# Schematic_Rev1.net
KiCad netlist of a schematic drawn in Altium Designer
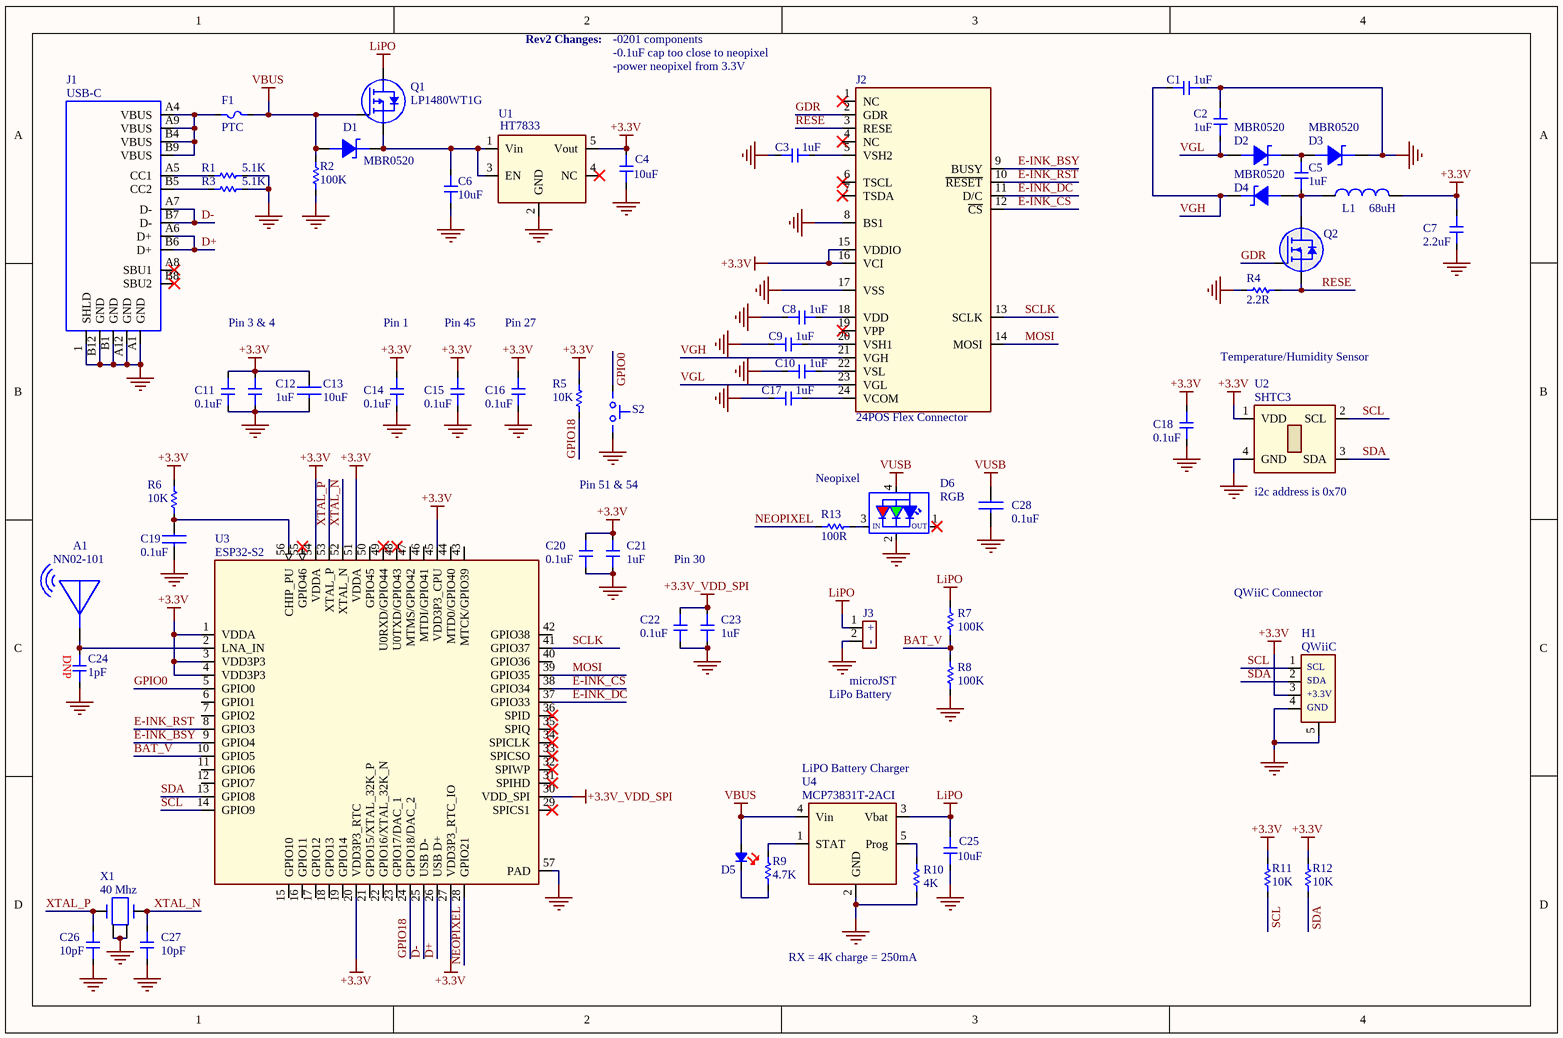
[diagram p0: Schematic_Rev1.SchDoc]

(export (version "E")
  (design (tool "Eeschema 10.0.6"))
  (components
    (comp (ref "A1")
      (value "NN02-101")
      (footprint "NN02-101")
      (description "Antenna Chip 2.4Gig")
      (fields (field (name "MANUFACTURER") "Ignion"))
      (libsource (lib "MAR") (part "NN02-101"))
    )
    (comp (ref "C1")
      (value "1uF")
      (footprint "CAPC1005X56N")
      (description "CAP 1uF 0402")
      (libsource (lib "MAR") (part "CAP_0402"))
    )
    (comp (ref "C2")
      (value "1uF")
      (footprint "CAPC1005X56N")
      (description "CAP 1uF 0402")
      (libsource (lib "MAR") (part "CAP_0402"))
    )
    (comp (ref "C3")
      (value "1uF")
      (footprint "CAPC1005X56N")
      (description "CAP 1uF 0402")
      (libsource (lib "MAR") (part "CAP_0402"))
    )
    (comp (ref "C4")
      (value "10uF")
      (footprint "CAPC2012X140N")
      (description "CAP 10uF 0805")
      (libsource (lib "MAR") (part "CAP_0805"))
    )
    (comp (ref "C5")
      (value "1uF")
      (footprint "CAPC1005X56N")
      (description "CAP 1uF 0402")
      (libsource (lib "MAR") (part "CAP_0402"))
    )
    (comp (ref "C6")
      (value "10uF")
      (footprint "CAPC2012X140N")
      (description "CAP 10uF 0805")
      (libsource (lib "MAR") (part "CAP_0805"))
    )
    (comp (ref "C7")
      (value "2.2uF")
      (footprint "CAPC1608X09L")
      (description "CAP 2.2uF 0603")
      (libsource (lib "MAR") (part "CAP_0402"))
    )
    (comp (ref "C8")
      (value "1uF")
      (footprint "CAPC1005X56N")
      (description "CAP 1uF 0402")
      (libsource (lib "MAR") (part "CAP_0402"))
    )
    (comp (ref "C9")
      (value "1uF")
      (footprint "CAPC1005X56N")
      (description "CAP 1uF 0402")
      (libsource (lib "MAR") (part "CAP_0402"))
    )
    (comp (ref "C10")
      (value "1uF")
      (footprint "CAPC1005X56N")
      (description "CAP 1uF 0402")
      (libsource (lib "MAR") (part "CAP_0402"))
    )
    (comp (ref "C11")
      (value "0.1uF")
      (footprint "CAPC1005X56N")
      (description "CAP 0.1uF 0402")
      (libsource (lib "MAR") (part "CAP_0402"))
    )
    (comp (ref "C12")
      (value "1uF")
      (footprint "CAPC1005X56N")
      (description "CAP 1uF 0402")
      (libsource (lib "MAR") (part "CAP_0402"))
    )
    (comp (ref "C13")
      (value "10uF")
      (footprint "CAPC2012X140N")
      (description "CAP 10uF 0805")
      (libsource (lib "") (part "CAP_0805_1"))
    )
    (comp (ref "C14")
      (value "0.1uF")
      (footprint "CAPC1005X56N")
      (description "CAP 0.1uF 0402")
      (libsource (lib "MAR") (part "CAP_0402"))
    )
    (comp (ref "C15")
      (value "0.1uF")
      (footprint "CAPC1005X56N")
      (description "CAP 0.1uF 0402")
      (libsource (lib "MAR") (part "CAP_0402"))
    )
    (comp (ref "C16")
      (value "0.1uF")
      (footprint "CAPC1005X56N")
      (description "CAP 0.1uF 0402")
      (libsource (lib "MAR") (part "CAP_0402"))
    )
    (comp (ref "C17")
      (value "1uF")
      (footprint "CAPC1005X56N")
      (description "CAP 1uF 0402")
      (libsource (lib "MAR") (part "CAP_0402"))
    )
    (comp (ref "C18")
      (value "0.1uF")
      (footprint "CAPC1005X56N")
      (description "CAP 0.1uF 0402")
      (libsource (lib "MAR") (part "CAP_0402"))
    )
    (comp (ref "C19")
      (value "0.1uF")
      (footprint "CAPC1005X56N")
      (description "CAP 0.1uF 0402")
      (fields (field (name "LCSC_PART_NUMBER") "C344190") (field (name "MANUFACTURER") "CCTC"))
      (libsource (lib "") (part "CAP_0402_1"))
    )
    (comp (ref "C20")
      (value "0.1uF")
      (footprint "CAPC1005X56N")
      (description "CAP 0.1uF 0402")
      (libsource (lib "MAR") (part "CAP_0402"))
    )
    (comp (ref "C21")
      (value "1uF")
      (footprint "CAPC1005X56N")
      (description "CAP 1uF 0402")
      (libsource (lib "MAR") (part "CAP_0402"))
    )
    (comp (ref "C22")
      (value "0.1uF")
      (footprint "CAPC1005X56N")
      (description "CAP 0.1uF 0402")
      (libsource (lib "MAR") (part "CAP_0402"))
    )
    (comp (ref "C23")
      (value "1uF")
      (footprint "CAPC1005X56N")
      (description "CAP 0.1uF 0402")
      (libsource (lib "MAR") (part "CAP_0402"))
    )
    (comp (ref "C24")
      (value "1pF")
      (footprint "CAPC1005X56N")
      (description "CAP 1pF 0402")
      (libsource (lib "MAR") (part "CAP_0402"))
    )
    (comp (ref "C25")
      (value "10uF")
      (footprint "CAPC2012X140N")
      (description "CAP 10uF 0805")
      (libsource (lib "MAR") (part "CAP_0805"))
    )
    (comp (ref "C26")
      (value "10pF")
      (footprint "CAPC1005X56N")
      (description "CAP 10pF 0402")
      (libsource (lib "MAR") (part "CAP_0402"))
    )
    (comp (ref "C27")
      (value "10pF")
      (footprint "CAPC1005X56N")
      (description "CAP 10pF 0402")
      (libsource (lib "MAR") (part "CAP_0402"))
    )
    (comp (ref "C28")
      (value "0.1uF")
      (footprint "CAPC1005X56N")
      (description "CAP 0.1uF 0402")
      (libsource (lib "") (part "CAP_0402_1"))
    )
    (comp (ref "D1")
      (value "MBR0520")
      (footprint "SOD123")
      (description "DIODE SCHOTTKY 20V 500MA SOD-123")
      (fields (field (name "MANUFACTURER") "Micro") (field (name "PART_NUMBER") "C78746"))
      (libsource (lib "MAR") (part "MBR0520-TP"))
    )
    (comp (ref "D2")
      (value "MBR0520")
      (footprint "SOD123")
      (description "DIODE SCHOTTKY 20V 500MA SOD-123")
      (fields (field (name "MANUFACTURER") "Micro") (field (name "PART_NUMBER") "C78746"))
      (libsource (lib "MAR") (part "MBR0520-TP"))
    )
    (comp (ref "D3")
      (value "MBR0520")
      (footprint "SOD123")
      (description "DIODE SCHOTTKY 20V 500MA SOD-123")
      (fields (field (name "MANUFACTURER") "Micro") (field (name "PART_NUMBER") "C78746"))
      (libsource (lib "MAR") (part "MBR0520-TP"))
    )
    (comp (ref "D4")
      (value "MBR0520")
      (footprint "SOD123")
      (description "DIODE SCHOTTKY 20V 500MA SOD-123")
      (fields (field (name "MANUFACTURER") "Micro") (field (name "PART_NUMBER") "C78746"))
      (libsource (lib "MAR") (part "MBR0520-TP"))
    )
    (comp (ref "D5")
      (value "Red Led")
      (footprint "LED1005X40N-Red")
      (description "LED Red 0402")
      (fields (field (name "PART_NUMBER") "C364556") (field (name "MANUFACTURER") "Lite-On"))
      (libsource (lib "MAR") (part "LED_0402_SMALL_Red"))
    )
    (comp (ref "D6")
      (value "RGB")
      (footprint "WS2812B-2020")
      (description "LED,RGB,NEOPIXEL,WS2818B 2020")
      (fields (field (name "PART_NUMBER") "4684") (field (name "MANUFACTURER") "Adafruit"))
      (libsource (lib "MAR") (part "WS2812B-2020"))
    )
    (comp (ref "F1")
      (value "TLC-PSMD050")
      (footprint "PTC2012X70L")
      (description "PTC FUSE 500mA hold, 1A trip")
      (fields (field (name "MANUFACTURER") "TLC") (field (name "PART_NUMBER") "C261942"))
      (libsource (lib "MAR") (part "PTC_FUSE"))
    )
    (comp (ref "H1")
      (value "QWiiC")
      (footprint "SM04B-SRSS-TB")
      (description "CONN HEADER 4POS .100 R/A QWIIC")
      (fields (field (name "MANUFACTURER") "JST") (field (name "PART_NUMBER") "PRT-14417"))
      (libsource (lib "MAR") (part "SM04B-SRSS-TB"))
    )
    (comp (ref "J1")
      (value "USB-C")
      (footprint "TYPE-C-31-M-12")
      (description "CONN RECPT USB-C")
      (fields (field (name "MANUFACTURER") "KHE") (field (name "PART_NUMBER") "C165948"))
      (libsource (lib "MAR") (part "USB-C"))
    )
    (comp (ref "J2")
      (value "24POS Flex Connector")
      (footprint "687124182122")
      (description "CONN FFC TOP/BOT 24POS 0.50MM R/A")
      (fields (field (name "MANUFACTURER") "Wurth") (field (name "PART_NUMBER") "687124182122"))
      (libsource (lib "MAR") (part "687124182122"))
    )
    (comp (ref "J3")
      (value "CON2")
      (footprint "JST_Micro_2PIN")
      (description "JST MIcro CONN 2POS")
      (libsource (lib "MAR") (part "JST_Micro_CONN_2PIN"))
    )
    (comp (ref "L1")
      (value "68uH")
      (footprint "INDUCTOR, 3mmX3mm")
      (description "INDUCTOR 68uH 20% 4mmx4mm")
      (fields (field (name "PART_NUMBER") "C135265") (field (name "MANUFACTURER") "SXN"))
      (libsource (lib "MAR") (part "68uH"))
    )
    (comp (ref "Q1")
      (value "LP1480WT1G")
      (footprint "SC-70")
      (description "MOSFET P-CH 20V 1.4A SC-70")
      (fields (field (name "MANUFACTURER") "LRC") (field (name "PART_NUMBER") "C172434"))
      (libsource (lib "MAR") (part "LP1480WT1G"))
    )
    (comp (ref "Q2")
      (value "~")
      (footprint "SOT95P240X110-3N")
      (description "MOSFET N-CH 60V 300MA SOT-23")
      (fields (field (name "MANUFACTURER") "Vishay Siliconix") (field (name "PART_NUMBER") "2N7002K-T1-E3"))
      (libsource (lib "MAR") (part "2N7002K-T1-E3"))
    )
    (comp (ref "R1")
      (value "5.1K")
      (footprint "RESC1005X40L (0402 FOOTPRINT)")
      (description "RES 5.1K 0402")
      (libsource (lib "MAR") (part "RES_0402"))
    )
    (comp (ref "R2")
      (value "100K")
      (footprint "RESC1005X40L (0402 FOOTPRINT)")
      (description "RES 100K 0402")
      (libsource (lib "MAR") (part "RES_0402"))
    )
    (comp (ref "R3")
      (value "5.1K")
      (footprint "RESC1005X40L (0402 FOOTPRINT)")
      (description "RES 5.1K 0402")
      (libsource (lib "MAR") (part "RES_0402"))
    )
    (comp (ref "R4")
      (value "2.2R")
      (footprint "RESC1005X40L (0402 FOOTPRINT)")
      (description "RES 2.2R 0402")
      (libsource (lib "MAR") (part "RES_0402"))
    )
    (comp (ref "R5")
      (value "10K")
      (footprint "RESC1005X40L (0402 FOOTPRINT)")
      (description "RES 10K 0402")
      (fields (field (name "LCSC_PART_NUMBER") "C258091") (field (name "MANUFACTURER") "Guangdong"))
      (libsource (lib "MAR") (part "RES_0402"))
    )
    (comp (ref "R6")
      (value "10K")
      (footprint "RESC1005X40L (0402 FOOTPRINT)")
      (description "RES 10K 0402")
      (fields (field (name "LCSC_PART_NUMBER") "C258091") (field (name "MANUFACTURER") "Guangdong"))
      (libsource (lib "MAR") (part "RES_0402"))
    )
    (comp (ref "R7")
      (value "100K")
      (footprint "RESC1005X40L (0402 FOOTPRINT)")
      (description "RES 100K 0402")
      (libsource (lib "MAR") (part "RES_0402"))
    )
    (comp (ref "R8")
      (value "100K")
      (footprint "RESC1005X40L (0402 FOOTPRINT)")
      (description "RES 100K 0402")
      (libsource (lib "MAR") (part "RES_0402"))
    )
    (comp (ref "R9")
      (value "4.7K")
      (footprint "RESC1005X40L (0402 FOOTPRINT)")
      (description "RES 4.7K 0402")
      (libsource (lib "MAR") (part "RES_0402"))
    )
    (comp (ref "R10")
      (value "4K")
      (footprint "RESC1005X40L (0402 FOOTPRINT)")
      (description "RES 4K 0402")
      (libsource (lib "MAR") (part "RES_0402"))
    )
    (comp (ref "R11")
      (value "10K")
      (footprint "RESC1005X40L (0402 FOOTPRINT)")
      (description "RES 10K 0402")
      (libsource (lib "MAR") (part "RES_0402"))
    )
    (comp (ref "R12")
      (value "10K")
      (footprint "RESC1005X40L (0402 FOOTPRINT)")
      (description "RES 10K 0402")
      (libsource (lib "MAR") (part "RES_0402"))
    )
    (comp (ref "R13")
      (value "100R")
      (footprint "RESC1005X40L (0402 FOOTPRINT)")
      (description "RES 100R 0402")
      (fields (field (name "MANUFACTURER") "Yageo") (field (name "PARTNUMBER") "C106232"))
      (libsource (lib "MAR") (part "RES_0603"))
    )
    (comp (ref "S2")
      (value "~")
      (footprint "TS-1088R-02526")
      (description "Tactile Micro Switch")
      (fields (field (name "PART_NUMBER") "C455281") (field (name "MANUFACTURER") "XUNPU"))
      (libsource (lib "MAR") (part "TS-1088R-02526"))
    )
    (comp (ref "U1")
      (value "HT7833")
      (footprint "SOT95P280X144-5N")
      (description "IC LDO 3.3V 0.5A SOT23-5")
      (fields (field (name "MANUFACTURER") "Holtek") (field (name "PART_NUMBER") "C164106"))
      (libsource (lib "MAR") (part "HT7833"))
    )
    (comp (ref "U2")
      (value "SHTC3")
      (footprint "DFN-4 (2.0mm X 2.0mm)")
      (description "Humidity/Temperature Sensor")
      (fields (field (name "MANUFACTURER") "Sensirion") (field (name "PART_NUMBER") "SHTC3"))
      (libsource (lib "MAR") (part "SHTC3"))
    )
    (comp (ref "U3")
      (value "ESP32-S2")
      (footprint "QFN56_0.4mm pitch")
      (description "WIFI/Bluetooth, QFN-56 7x7")
      (fields (field (name "MANUFACTURER") "Espressif") (field (name "PART_NUMBER") "C529594"))
      (libsource (lib "MAR") (part "ESP32-S2"))
    )
    (comp (ref "U4")
      (value "MCP73831T-2ACI")
      (footprint "SOT95P280X144-5N")
      (description "Charger IC Lithium-Ion/Polymer SOT23-5")
      (fields (field (name "MANUFACTURER") "Microchip") (field (name "PART_NUMBER") "MCP73831T-2ACI/OT"))
      (libsource (lib "MAR") (part "MCP73831T-2ACI/OT"))
    )
    (comp (ref "X1")
      (value "40 Mhz")
      (footprint "OSC20X16")
      (description "CRYSTAL 40MHZ 10PF SMD")
      (fields (field (name "PART_NUMBER") "ECS-400-10-37B2-CKM") (field (name "MANUFACTURER") "ECS"))
      (libsource (lib "MAR") (part "40Mhz"))
    )
  )
  (nets
    (net (code "1") (name "+3.3V") (class "Default")
      (node (ref "C11") (pin "1") (pintype "passive"))
      (node (ref "C12") (pin "1") (pintype "passive"))
      (node (ref "C13") (pin "1") (pinfunction "1_1") (pintype "passive"))
      (node (ref "C14") (pin "1") (pintype "passive"))
      (node (ref "C15") (pin "1") (pintype "passive"))
      (node (ref "C16") (pin "1") (pintype "passive"))
      (node (ref "C18") (pin "1") (pintype "passive"))
      (node (ref "C20") (pin "1") (pintype "passive"))
      (node (ref "C21") (pin "1") (pintype "passive"))
      (node (ref "C4") (pin "1") (pintype "passive"))
      (node (ref "C7") (pin "1") (pintype "passive"))
      (node (ref "H1") (pin "3") (pintype "passive"))
      (node (ref "J2") (pin "15") (pinfunction "VDDIO_15") (pintype "power_in"))
      (node (ref "J2") (pin "16") (pinfunction "VCI_16") (pintype "power_in"))
      (node (ref "L1") (pin "2") (pinfunction "2_2") (pintype "passive"))
      (node (ref "R11") (pin "2") (pintype "passive"))
      (node (ref "R12") (pin "2") (pintype "passive"))
      (node (ref "R5") (pin "1") (pintype "passive"))
      (node (ref "R6") (pin "1") (pintype "passive"))
      (node (ref "U1") (pin "5") (pinfunction "Vout_5") (pintype "passive"))
      (node (ref "U2") (pin "1") (pinfunction "VDD_1") (pintype "power_in"))
      (node (ref "U3") (pin "1") (pinfunction "VDDA_1") (pintype "power_in"))
      (node (ref "U3") (pin "20") (pinfunction "VDD3P3_RTC_20") (pintype "power_in"))
      (node (ref "U3") (pin "27") (pinfunction "VDD3P3_RTC_IO_27") (pintype "power_in"))
      (node (ref "U3") (pin "3") (pinfunction "VDD3P3_3") (pintype "power_in"))
      (node (ref "U3") (pin "4") (pinfunction "VDD3P3_4") (pintype "power_in"))
      (node (ref "U3") (pin "45") (pinfunction "VDD3P3_CPU_45") (pintype "power_in"))
      (node (ref "U3") (pin "51") (pinfunction "VDDA_51") (pintype "power_in"))
      (node (ref "U3") (pin "54") (pinfunction "VDDA_54") (pintype "power_in"))
    )
    (net (code "2") (name "+3.3V_VDD_SPI") (class "Default")
      (node (ref "C22") (pin "1") (pintype "passive"))
      (node (ref "C23") (pin "1") (pintype "passive"))
      (node (ref "U3") (pin "30") (pinfunction "VDD_SPI_30") (pintype "power_in"))
    )
    (net (code "3") (name "/BAT_V") (class "Default")
      (node (ref "R7") (pin "1") (pintype "passive"))
      (node (ref "R8") (pin "2") (pintype "passive"))
      (node (ref "U3") (pin "10") (pinfunction "GPIO5_10") (pintype "passive"))
    )
    (net (code "4") (name "/D+") (class "Default")
      (node (ref "J1") (pin "A6") (pinfunction "D+_A6") (pintype "power_in"))
      (node (ref "J1") (pin "B6") (pinfunction "D+_B6") (pintype "power_in"))
      (node (ref "U3") (pin "26") (pinfunction "USB_D+_26") (pintype "passive"))
    )
    (net (code "5") (name "/D-") (class "Default")
      (node (ref "J1") (pin "A7") (pinfunction "D-_A7") (pintype "power_in"))
      (node (ref "J1") (pin "B7") (pinfunction "D-_B7") (pintype "power_in"))
      (node (ref "U3") (pin "25") (pinfunction "USB_D-_25") (pintype "passive"))
    )
    (net (code "6") (name "/E-INK_BSY") (class "Default")
      (node (ref "J2") (pin "9") (pinfunction "BUSY_9") (pintype "passive"))
      (node (ref "U3") (pin "9") (pinfunction "GPIO4_9") (pintype "passive"))
    )
    (net (code "7") (name "/E-INK_CS") (class "Default")
      (node (ref "J2") (pin "12") (pinfunction "~{CS}_12") (pintype "passive"))
      (node (ref "U3") (pin "38") (pinfunction "GPIO34_38") (pintype "passive"))
    )
    (net (code "8") (name "/E-INK_DC") (class "Default")
      (node (ref "J2") (pin "11") (pinfunction "D/C_11") (pintype "passive"))
      (node (ref "U3") (pin "37") (pinfunction "GPIO33_37") (pintype "passive"))
    )
    (net (code "9") (name "/E-INK_RST") (class "Default")
      (node (ref "J2") (pin "10") (pinfunction "~{RESET}_10") (pintype "passive"))
      (node (ref "U3") (pin "8") (pinfunction "GPIO3_8") (pintype "passive"))
    )
    (net (code "10") (name "/GDR") (class "Default")
      (node (ref "J2") (pin "2") (pinfunction "GDR_2") (pintype "passive"))
      (node (ref "Q2") (pin "1") (pinfunction "G_1") (pintype "passive"))
    )
    (net (code "11") (name "/GPIO0") (class "Default")
      (node (ref "S2") (pin "1") (pinfunction "A_1") (pintype "passive"))
      (node (ref "U3") (pin "5") (pinfunction "GPIO0_5") (pintype "passive"))
    )
    (net (code "12") (name "/GPIO18") (class "Default")
      (node (ref "R5") (pin "2") (pintype "passive"))
      (node (ref "U3") (pin "24") (pinfunction "GPIO18/DAC_2_24") (pintype "passive"))
    )
    (net (code "13") (name "/MOSI") (class "Default")
      (node (ref "J2") (pin "14") (pinfunction "MOSI_14") (pintype "passive"))
      (node (ref "U3") (pin "39") (pinfunction "GPIO35_39") (pintype "passive"))
    )
    (net (code "14") (name "/NEOPIXEL") (class "Default")
      (node (ref "R13") (pin "2") (pintype "passive"))
      (node (ref "U3") (pin "28") (pinfunction "GPIO21_28") (pintype "passive"))
    )
    (net (code "15") (name "/RESE") (class "Default")
      (node (ref "J2") (pin "3") (pinfunction "RESE_3") (pintype "passive"))
      (node (ref "Q2") (pin "2") (pinfunction "S_2") (pintype "passive"))
      (node (ref "R4") (pin "1") (pintype "passive"))
    )
    (net (code "16") (name "/SCL") (class "Default")
      (node (ref "H1") (pin "1") (pintype "passive"))
      (node (ref "R11") (pin "1") (pintype "passive"))
      (node (ref "U2") (pin "2") (pinfunction "SCL_2") (pintype "passive"))
      (node (ref "U3") (pin "14") (pinfunction "GPIO9_14") (pintype "passive"))
    )
    (net (code "17") (name "/SCLK") (class "Default")
      (node (ref "J2") (pin "13") (pinfunction "SCLK_13") (pintype "passive"))
      (node (ref "U3") (pin "41") (pinfunction "GPIO37_41") (pintype "passive"))
    )
    (net (code "18") (name "/SDA") (class "Default")
      (node (ref "H1") (pin "2") (pintype "passive"))
      (node (ref "R12") (pin "1") (pintype "passive"))
      (node (ref "U2") (pin "3") (pinfunction "SDA_3") (pintype "passive"))
      (node (ref "U3") (pin "13") (pinfunction "GPIO8_13") (pintype "passive"))
    )
    (net (code "19") (name "/VGH") (class "Default")
      (node (ref "C1") (pin "1") (pintype "passive"))
      (node (ref "D4") (pin "1") (pinfunction "Cathode_1") (pintype "passive"))
      (node (ref "J2") (pin "21") (pinfunction "VGH_21") (pintype "passive"))
    )
    (net (code "20") (name "/VGL") (class "Default")
      (node (ref "C2") (pin "2") (pintype "passive"))
      (node (ref "D2") (pin "2") (pinfunction "Annode_2") (pintype "passive"))
      (node (ref "J2") (pin "23") (pinfunction "VGL_23") (pintype "passive"))
    )
    (net (code "21") (name "/XTAL_N") (class "Default")
      (node (ref "C27") (pin "1") (pintype "passive"))
      (node (ref "U3") (pin "52") (pinfunction "XTAL_N_52") (pintype "passive"))
      (node (ref "X1") (pin "3") (pinfunction "3_3") (pintype "passive"))
    )
    (net (code "22") (name "/XTAL_P") (class "Default")
      (node (ref "C26") (pin "1") (pintype "passive"))
      (node (ref "U3") (pin "53") (pinfunction "XTAL_P_53") (pintype "passive"))
      (node (ref "X1") (pin "1") (pinfunction "1_1") (pintype "passive"))
    )
    (net (code "23") (name "GND") (class "Default")
      (node (ref "C1") (pin "2") (pintype "passive"))
      (node (ref "C10") (pin "1") (pintype "passive"))
      (node (ref "C11") (pin "2") (pintype "passive"))
      (node (ref "C12") (pin "2") (pintype "passive"))
      (node (ref "C13") (pin "2") (pinfunction "2_2") (pintype "passive"))
      (node (ref "C14") (pin "2") (pintype "passive"))
      (node (ref "C15") (pin "2") (pintype "passive"))
      (node (ref "C16") (pin "2") (pintype "passive"))
      (node (ref "C17") (pin "1") (pintype "passive"))
      (node (ref "C18") (pin "2") (pintype "passive"))
      (node (ref "C19") (pin "2") (pinfunction "2_2") (pintype "passive"))
      (node (ref "C2") (pin "1") (pintype "passive"))
      (node (ref "C20") (pin "2") (pintype "passive"))
      (node (ref "C21") (pin "2") (pintype "passive"))
      (node (ref "C22") (pin "2") (pintype "passive"))
      (node (ref "C23") (pin "2") (pintype "passive"))
      (node (ref "C24") (pin "2") (pintype "passive"))
      (node (ref "C25") (pin "2") (pintype "passive"))
      (node (ref "C26") (pin "2") (pintype "passive"))
      (node (ref "C27") (pin "2") (pintype "passive"))
      (node (ref "C28") (pin "2") (pinfunction "2_2") (pintype "passive"))
      (node (ref "C3") (pin "1") (pintype "passive"))
      (node (ref "C4") (pin "2") (pintype "passive"))
      (node (ref "C6") (pin "2") (pintype "passive"))
      (node (ref "C7") (pin "2") (pintype "passive"))
      (node (ref "C8") (pin "1") (pintype "passive"))
      (node (ref "C9") (pin "1") (pintype "passive"))
      (node (ref "D3") (pin "1") (pinfunction "Cathode_1") (pintype "passive"))
      (node (ref "D6") (pin "2") (pinfunction "GND_2") (pintype "passive"))
      (node (ref "H1") (pin "4") (pintype "passive"))
      (node (ref "H1") (pin "5") (pintype "passive"))
      (node (ref "J1") (pin "1") (pinfunction "SHLD_1") (pintype "power_in"))
      (node (ref "J1") (pin "A1") (pinfunction "GND_A1") (pintype "power_in"))
      (node (ref "J1") (pin "A12") (pinfunction "GND_A12") (pintype "power_in"))
      (node (ref "J1") (pin "B1") (pinfunction "GND_B1") (pintype "power_in"))
      (node (ref "J1") (pin "B12") (pinfunction "GND_B12") (pintype "passive"))
      (node (ref "J2") (pin "17") (pinfunction "VSS_17") (pintype "power_in"))
      (node (ref "J2") (pin "8") (pinfunction "BS1_8") (pintype "passive"))
      (node (ref "J3") (pin "2") (pintype "passive"))
      (node (ref "R1") (pin "1") (pintype "passive"))
      (node (ref "R10") (pin "1") (pintype "passive"))
      (node (ref "R2") (pin "2") (pintype "passive"))
      (node (ref "R3") (pin "1") (pintype "passive"))
      (node (ref "R4") (pin "2") (pintype "passive"))
      (node (ref "R8") (pin "1") (pintype "passive"))
      (node (ref "S2") (pin "2") (pinfunction "B_2") (pintype "passive"))
      (node (ref "U1") (pin "2") (pinfunction "GND_2") (pintype "power_in"))
      (node (ref "U2") (pin "4") (pinfunction "GND_4") (pintype "power_in"))
      (node (ref "U3") (pin "57") (pinfunction "PAD_57") (pintype "power_in"))
      (node (ref "U4") (pin "2") (pinfunction "GND_2") (pintype "power_in"))
      (node (ref "X1") (pin "2") (pinfunction "2_2") (pintype "power_in"))
      (node (ref "X1") (pin "4") (pinfunction "4_4") (pintype "power_in"))
    )
    (net (code "24") (name "LiPO") (class "Default")
      (node (ref "C25") (pin "1") (pintype "passive"))
      (node (ref "J3") (pin "1") (pintype "passive"))
      (node (ref "Q1") (pin "3") (pinfunction "D_3") (pintype "passive"))
      (node (ref "R7") (pin "2") (pintype "passive"))
      (node (ref "U4") (pin "3") (pinfunction "Vbat_3") (pintype "passive"))
    )
    (net (code "25") (name "Net-(D1-Cathode)") (class "Default")
      (node (ref "C6") (pin "1") (pintype "passive"))
      (node (ref "D1") (pin "1") (pinfunction "Cathode_1") (pintype "passive"))
      (node (ref "Q1") (pin "2") (pinfunction "S_2") (pintype "passive"))
      (node (ref "U1") (pin "1") (pinfunction "Vin_1") (pintype "passive"))
      (node (ref "U1") (pin "3") (pinfunction "EN_3") (pintype "passive"))
    )
    (net (code "26") (name "Net-(D2-Cathode)") (class "Default")
      (node (ref "C5") (pin "1") (pintype "passive"))
      (node (ref "D2") (pin "1") (pinfunction "Cathode_1") (pintype "passive"))
      (node (ref "D3") (pin "2") (pinfunction "Annode_2") (pintype "passive"))
    )
    (net (code "27") (name "Net-(D4-Annode)") (class "Default")
      (node (ref "C5") (pin "2") (pintype "passive"))
      (node (ref "D4") (pin "2") (pinfunction "Annode_2") (pintype "passive"))
      (node (ref "L1") (pin "1") (pinfunction "1_1") (pintype "passive"))
      (node (ref "Q2") (pin "3") (pinfunction "D_3") (pintype "passive"))
    )
    (net (code "28") (name "Net-(D5-Pad1)") (class "Default")
      (node (ref "D5") (pin "1") (pintype "passive"))
      (node (ref "R9") (pin "1") (pintype "passive"))
    )
    (net (code "29") (name "Net-(D6-DIN)") (class "Default")
      (node (ref "D6") (pin "3") (pinfunction "DIN_3") (pintype "passive"))
      (node (ref "R13") (pin "1") (pintype "passive"))
    )
    (net (code "30") (name "Net-(F1-Pad2)") (class "Default")
      (node (ref "F1") (pin "2") (pintype "passive"))
      (node (ref "J1") (pin "A4") (pinfunction "VBUS_A4") (pintype "passive"))
      (node (ref "J1") (pin "A9") (pinfunction "VBUS_A9") (pintype "power_in"))
      (node (ref "J1") (pin "B4") (pinfunction "VBUS_B4") (pintype "power_in"))
      (node (ref "J1") (pin "B9") (pinfunction "VBUS_B9") (pintype "passive"))
    )
    (net (code "31") (name "Net-(J1-CC1)") (class "Default")
      (node (ref "J1") (pin "A5") (pinfunction "CC1_A5") (pintype "power_in"))
      (node (ref "R1") (pin "2") (pintype "passive"))
    )
    (net (code "32") (name "Net-(J1-CC2)") (class "Default")
      (node (ref "J1") (pin "B5") (pinfunction "CC2_B5") (pintype "power_in"))
      (node (ref "R3") (pin "2") (pintype "passive"))
    )
    (net (code "33") (name "Net-(J2-VCOM)") (class "Default")
      (node (ref "C17") (pin "2") (pintype "passive"))
      (node (ref "J2") (pin "24") (pinfunction "VCOM_24") (pintype "passive"))
    )
    (net (code "34") (name "Net-(J2-VDD)") (class "Default")
      (node (ref "C8") (pin "2") (pintype "passive"))
      (node (ref "J2") (pin "18") (pinfunction "VDD_18") (pintype "power_in"))
    )
    (net (code "35") (name "Net-(J2-VSH1)") (class "Default")
      (node (ref "C9") (pin "2") (pintype "passive"))
      (node (ref "J2") (pin "20") (pinfunction "VSH1_20") (pintype "passive"))
    )
    (net (code "36") (name "Net-(J2-VSH2)") (class "Default")
      (node (ref "C3") (pin "2") (pintype "passive"))
      (node (ref "J2") (pin "5") (pinfunction "VSH2_5") (pintype "passive"))
    )
    (net (code "37") (name "Net-(J2-VSL)") (class "Default")
      (node (ref "C10") (pin "2") (pintype "passive"))
      (node (ref "J2") (pin "22") (pinfunction "VSL_22") (pintype "passive"))
    )
    (net (code "38") (name "Net-(U3-CHIP_PU)") (class "Default")
      (node (ref "C19") (pin "1") (pinfunction "1_1") (pintype "passive"))
      (node (ref "R6") (pin "2") (pintype "passive"))
      (node (ref "U3") (pin "56") (pinfunction "CHIP_PU_56") (pintype "input"))
    )
    (net (code "39") (name "Net-(U3-LNA_IN)") (class "Default")
      (node (ref "A1") (pin "1") (pintype "passive"))
      (node (ref "C24") (pin "1") (pintype "passive"))
      (node (ref "U3") (pin "2") (pinfunction "LNA_IN_2") (pintype "passive"))
    )
    (net (code "40") (name "Net-(U4-Prog)") (class "Default")
      (node (ref "R10") (pin "2") (pintype "passive"))
      (node (ref "U4") (pin "5") (pinfunction "Prog_5") (pintype "passive"))
    )
    (net (code "41") (name "Net-(U4-STAT)") (class "Default")
      (node (ref "R9") (pin "2") (pintype "passive"))
      (node (ref "U4") (pin "1") (pinfunction "STAT_1") (pintype "passive"))
    )
    (net (code "42") (name "VBUS") (class "Default")
      (node (ref "D1") (pin "2") (pinfunction "Annode_2") (pintype "passive"))
      (node (ref "D5") (pin "2") (pintype "passive"))
      (node (ref "F1") (pin "1") (pintype "passive"))
      (node (ref "Q1") (pin "1") (pinfunction "G_1") (pintype "passive"))
      (node (ref "R2") (pin "1") (pintype "passive"))
      (node (ref "U4") (pin "4") (pinfunction "Vin_4") (pintype "passive"))
    )
    (net (code "43") (name "VUSB") (class "Default")
      (node (ref "C28") (pin "1") (pinfunction "1_1") (pintype "passive"))
      (node (ref "D6") (pin "4") (pinfunction "VDD_4") (pintype "passive"))
    )
    (net (code "44") (name "unconnected-(D6-DOUT-Pad1)") (class "Default")
      (node (ref "D6") (pin "1") (pinfunction "DOUT_1") (pintype "passive+no_connect"))
    )
    (net (code "45") (name "unconnected-(J1-SBU1-PadA8)") (class "Default")
      (node (ref "J1") (pin "A8") (pinfunction "SBU1_A8") (pintype "power_in+no_connect"))
    )
    (net (code "46") (name "unconnected-(J1-SBU2-PadB8)") (class "Default")
      (node (ref "J1") (pin "B8") (pinfunction "SBU2_B8") (pintype "power_in+no_connect"))
    )
    (net (code "47") (name "unconnected-(J2-NC-Pad1)") (class "Default")
      (node (ref "J2") (pin "1") (pinfunction "NC_1") (pintype "passive+no_connect"))
    )
    (net (code "48") (name "unconnected-(J2-NC-Pad4)") (class "Default")
      (node (ref "J2") (pin "4") (pinfunction "NC_4") (pintype "passive+no_connect"))
    )
    (net (code "49") (name "unconnected-(J2-TSCL-Pad6)") (class "Default")
      (node (ref "J2") (pin "6") (pinfunction "TSCL_6") (pintype "passive+no_connect"))
    )
    (net (code "50") (name "unconnected-(J2-TSDA-Pad7)") (class "Default")
      (node (ref "J2") (pin "7") (pinfunction "TSDA_7") (pintype "passive+no_connect"))
    )
    (net (code "51") (name "unconnected-(J2-VPP-Pad19)") (class "Default")
      (node (ref "J2") (pin "19") (pinfunction "VPP_19") (pintype "passive+no_connect"))
    )
    (net (code "52") (name "unconnected-(U1-NC-Pad4)") (class "Default")
      (node (ref "U1") (pin "4") (pinfunction "NC_4") (pintype "passive+no_connect"))
    )
    (net (code "53") (name "unconnected-(U3-GPIO1-Pad6)") (class "Default")
      (node (ref "U3") (pin "6") (pinfunction "GPIO1_6") (pintype "passive"))
    )
    (net (code "54") (name "unconnected-(U3-GPIO2-Pad7)") (class "Default")
      (node (ref "U3") (pin "7") (pinfunction "GPIO2_7") (pintype "passive"))
    )
    (net (code "55") (name "unconnected-(U3-GPIO6-Pad11)") (class "Default")
      (node (ref "U3") (pin "11") (pinfunction "GPIO6_11") (pintype "passive"))
    )
    (net (code "56") (name "unconnected-(U3-GPIO7-Pad12)") (class "Default")
      (node (ref "U3") (pin "12") (pinfunction "GPIO7_12") (pintype "passive"))
    )
    (net (code "57") (name "unconnected-(U3-GPIO10-Pad15)") (class "Default")
      (node (ref "U3") (pin "15") (pinfunction "GPIO10_15") (pintype "passive"))
    )
    (net (code "58") (name "unconnected-(U3-GPIO11-Pad16)") (class "Default")
      (node (ref "U3") (pin "16") (pinfunction "GPIO11_16") (pintype "passive"))
    )
    (net (code "59") (name "unconnected-(U3-GPIO12-Pad17)") (class "Default")
      (node (ref "U3") (pin "17") (pinfunction "GPIO12_17") (pintype "passive"))
    )
    (net (code "60") (name "unconnected-(U3-GPIO13-Pad18)") (class "Default")
      (node (ref "U3") (pin "18") (pinfunction "GPIO13_18") (pintype "passive"))
    )
    (net (code "61") (name "unconnected-(U3-GPIO14-Pad19)") (class "Default")
      (node (ref "U3") (pin "19") (pinfunction "GPIO14_19") (pintype "passive"))
    )
    (net (code "62") (name "unconnected-(U3-GPIO15{slash}XTAL_32K_P-Pad21)") (class "Default")
      (node (ref "U3") (pin "21") (pinfunction "GPIO15/XTAL_32K_P_21") (pintype "passive"))
    )
    (net (code "63") (name "unconnected-(U3-GPIO16{slash}XTAL_32K_N-Pad22)") (class "Default")
      (node (ref "U3") (pin "22") (pinfunction "GPIO16/XTAL_32K_N_22") (pintype "passive"))
    )
    (net (code "64") (name "unconnected-(U3-GPIO17{slash}DAC_1-Pad23)") (class "Default")
      (node (ref "U3") (pin "23") (pinfunction "GPIO17/DAC_1_23") (pintype "passive"))
    )
    (net (code "65") (name "unconnected-(U3-GPIO36-Pad40)") (class "Default")
      (node (ref "U3") (pin "40") (pinfunction "GPIO36_40") (pintype "passive"))
    )
    (net (code "66") (name "unconnected-(U3-GPIO38-Pad42)") (class "Default")
      (node (ref "U3") (pin "42") (pinfunction "GPIO38_42") (pintype "passive"))
    )
    (net (code "67") (name "unconnected-(U3-GPIO45-Pad50)") (class "Default")
      (node (ref "U3") (pin "50") (pinfunction "GPIO45_50") (pintype "passive"))
    )
    (net (code "68") (name "unconnected-(U3-GPIO46-Pad55)") (class "Default")
      (node (ref "U3") (pin "55") (pinfunction "GPIO46_55") (pintype "input+no_connect"))
    )
    (net (code "69") (name "unconnected-(U3-MTCK{slash}GPIO39-Pad43)") (class "Default")
      (node (ref "U3") (pin "43") (pinfunction "MTCK/GPIO39_43") (pintype "passive"))
    )
    (net (code "70") (name "unconnected-(U3-MTD0{slash}GPIO40-Pad44)") (class "Default")
      (node (ref "U3") (pin "44") (pinfunction "MTD0/GPIO40_44") (pintype "passive"))
    )
    (net (code "71") (name "unconnected-(U3-MTDI{slash}GPIO41-Pad46)") (class "Default")
      (node (ref "U3") (pin "46") (pinfunction "MTDI/GPIO41_46") (pintype "passive"))
    )
    (net (code "72") (name "unconnected-(U3-MTMS{slash}GPIO42-Pad47)") (class "Default")
      (node (ref "U3") (pin "47") (pinfunction "MTMS/GPIO42_47") (pintype "passive"))
    )
    (net (code "73") (name "unconnected-(U3-SPICLK-Pad34)") (class "Default")
      (node (ref "U3") (pin "34") (pinfunction "SPICLK_34") (pintype "passive+no_connect"))
    )
    (net (code "74") (name "unconnected-(U3-SPICS1-Pad29)") (class "Default")
      (node (ref "U3") (pin "29") (pinfunction "SPICS1_29") (pintype "passive+no_connect"))
    )
    (net (code "75") (name "unconnected-(U3-SPICSO-Pad33)") (class "Default")
      (node (ref "U3") (pin "33") (pinfunction "SPICSO_33") (pintype "passive+no_connect"))
    )
    (net (code "76") (name "unconnected-(U3-SPID-Pad36)") (class "Default")
      (node (ref "U3") (pin "36") (pinfunction "SPID_36") (pintype "passive+no_connect"))
    )
    (net (code "77") (name "unconnected-(U3-SPIHD-Pad31)") (class "Default")
      (node (ref "U3") (pin "31") (pinfunction "SPIHD_31") (pintype "passive+no_connect"))
    )
    (net (code "78") (name "unconnected-(U3-SPIQ-Pad35)") (class "Default")
      (node (ref "U3") (pin "35") (pinfunction "SPIQ_35") (pintype "passive+no_connect"))
    )
    (net (code "79") (name "unconnected-(U3-SPIWP-Pad32)") (class "Default")
      (node (ref "U3") (pin "32") (pinfunction "SPIWP_32") (pintype "passive+no_connect"))
    )
    (net (code "80") (name "unconnected-(U3-U0RXD{slash}GPIO44-Pad49)") (class "Default")
      (node (ref "U3") (pin "49") (pinfunction "U0RXD/GPIO44_49") (pintype "passive+no_connect"))
    )
    (net (code "81") (name "unconnected-(U3-U0TXD{slash}GPIO43-Pad48)") (class "Default")
      (node (ref "U3") (pin "48") (pinfunction "U0TXD/GPIO43_48") (pintype "passive+no_connect"))
    )
  )
)
